# manual_master.net
KiCad netlist of a schematic drawn in EAGLE
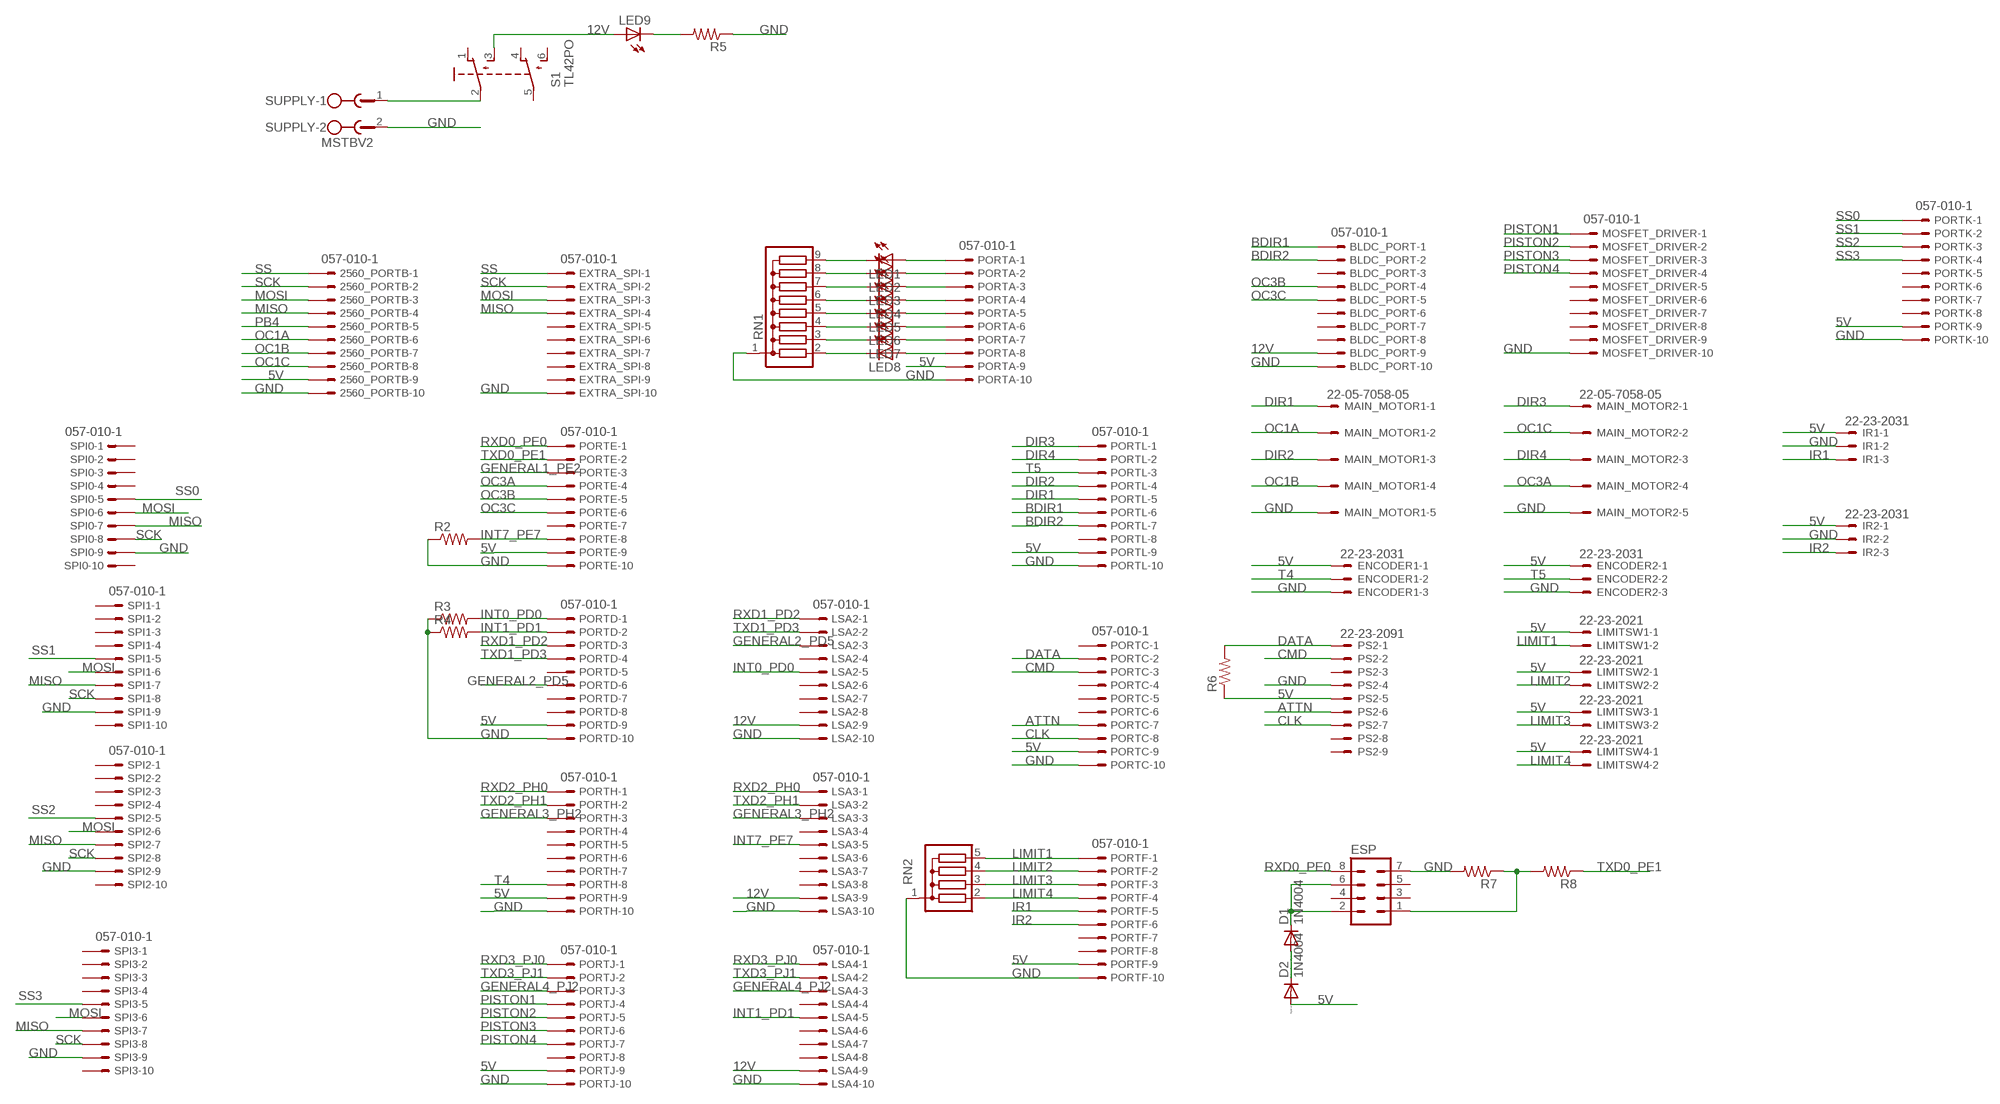
[diagram p0: schematic, sheet 1]

(export (version "E")
  (design (tool "Eeschema 10.0.6"))
  (components
    (comp (ref "2560_PORTB")
      (value "057-010-1")
      (footprint "eagle-import:057-010-1")
      (libsource (lib "eagle-import") (part "057-010-1"))
    )
    (comp (ref "BLDC_PORT")
      (value "057-010-1")
      (footprint "eagle-import:057-010-1")
      (libsource (lib "eagle-import") (part "057-010-1"))
    )
    (comp (ref "D1")
      (value "1N4004")
      (footprint "eagle-import:DO41-10")
      (libsource (lib "eagle-import") (part "1N4004"))
    )
    (comp (ref "D2")
      (value "1N4004")
      (footprint "eagle-import:DO41-10")
      (libsource (lib "eagle-import") (part "1N4004"))
    )
    (comp (ref "ENCODER1")
      (value "22-23-2031")
      (footprint "eagle-import:22-23-2031")
      (fields (field (name "MF") "MOLEX"))
      (libsource (lib "eagle-import") (part "22-23-2031"))
    )
    (comp (ref "ENCODER2")
      (value "22-23-2031")
      (footprint "eagle-import:22-23-2031")
      (fields (field (name "MF") "MOLEX"))
      (libsource (lib "eagle-import") (part "22-23-2031"))
    )
    (comp (ref "ESP")
      (value "MA04-2")
      (footprint "eagle-import:MA04-2")
      (libsource (lib "eagle-import") (part "MA04-2"))
    )
    (comp (ref "EXTRA_SPI")
      (value "057-010-1")
      (footprint "eagle-import:057-010-1")
      (libsource (lib "eagle-import") (part "057-010-1"))
    )
    (comp (ref "IR1")
      (value "22-23-2031")
      (footprint "eagle-import:22-23-2031")
      (fields (field (name "MF") "MOLEX"))
      (libsource (lib "eagle-import") (part "22-23-2031"))
    )
    (comp (ref "IR2")
      (value "22-23-2031")
      (footprint "eagle-import:22-23-2031")
      (fields (field (name "MF") "MOLEX"))
      (libsource (lib "eagle-import") (part "22-23-2031"))
    )
    (comp (ref "LED1")
      (value "LED3MM")
      (footprint "eagle-import:LED3MM")
      (libsource (lib "eagle-import") (part "LED3MM"))
    )
    (comp (ref "LED2")
      (value "LED3MM")
      (footprint "eagle-import:LED3MM")
      (libsource (lib "eagle-import") (part "LED3MM"))
    )
    (comp (ref "LED3")
      (value "LED3MM")
      (footprint "eagle-import:LED3MM")
      (libsource (lib "eagle-import") (part "LED3MM"))
    )
    (comp (ref "LED4")
      (value "LED3MM")
      (footprint "eagle-import:LED3MM")
      (libsource (lib "eagle-import") (part "LED3MM"))
    )
    (comp (ref "LED5")
      (value "LED3MM")
      (footprint "eagle-import:LED3MM")
      (libsource (lib "eagle-import") (part "LED3MM"))
    )
    (comp (ref "LED6")
      (value "LED3MM")
      (footprint "eagle-import:LED3MM")
      (libsource (lib "eagle-import") (part "LED3MM"))
    )
    (comp (ref "LED7")
      (value "LED3MM")
      (footprint "eagle-import:LED3MM")
      (libsource (lib "eagle-import") (part "LED3MM"))
    )
    (comp (ref "LED8")
      (value "LED3MM")
      (footprint "eagle-import:LED3MM")
      (libsource (lib "eagle-import") (part "LED3MM"))
    )
    (comp (ref "LED9")
      (value "LED5MM")
      (footprint "eagle-import:LED5MM")
      (libsource (lib "eagle-import") (part "LED5MM"))
    )
    (comp (ref "LIMITSW1")
      (value "22-23-2021")
      (footprint "eagle-import:22-23-2021")
      (fields (field (name "MF") "MOLEX"))
      (libsource (lib "eagle-import") (part "22-23-2021"))
    )
    (comp (ref "LIMITSW2")
      (value "22-23-2021")
      (footprint "eagle-import:22-23-2021")
      (fields (field (name "MF") "MOLEX"))
      (libsource (lib "eagle-import") (part "22-23-2021"))
    )
    (comp (ref "LIMITSW3")
      (value "22-23-2021")
      (footprint "eagle-import:22-23-2021")
      (fields (field (name "MF") "MOLEX"))
      (libsource (lib "eagle-import") (part "22-23-2021"))
    )
    (comp (ref "LIMITSW4")
      (value "22-23-2021")
      (footprint "eagle-import:22-23-2021")
      (fields (field (name "MF") "MOLEX"))
      (libsource (lib "eagle-import") (part "22-23-2021"))
    )
    (comp (ref "LSA2")
      (value "057-010-1")
      (footprint "eagle-import:057-010-1")
      (libsource (lib "eagle-import") (part "057-010-1"))
    )
    (comp (ref "LSA3")
      (value "057-010-1")
      (footprint "eagle-import:057-010-1")
      (libsource (lib "eagle-import") (part "057-010-1"))
    )
    (comp (ref "LSA4")
      (value "057-010-1")
      (footprint "eagle-import:057-010-1")
      (libsource (lib "eagle-import") (part "057-010-1"))
    )
    (comp (ref "MAIN_MOTOR1")
      (value "22-05-7058-05")
      (footprint "eagle-import:7395-05")
      (libsource (lib "eagle-import") (part "22-?-0505-7058"))
    )
    (comp (ref "MAIN_MOTOR2")
      (value "22-05-7058-05")
      (footprint "eagle-import:7395-05")
      (libsource (lib "eagle-import") (part "22-?-0505-7058"))
    )
    (comp (ref "MOSFET_DRIVER")
      (value "057-010-1")
      (footprint "eagle-import:057-010-1")
      (libsource (lib "eagle-import") (part "057-010-1"))
    )
    (comp (ref "PORTA")
      (value "057-010-1")
      (footprint "eagle-import:057-010-1")
      (libsource (lib "eagle-import") (part "057-010-1"))
    )
    (comp (ref "PORTC")
      (value "057-010-1")
      (footprint "eagle-import:057-010-1")
      (libsource (lib "eagle-import") (part "057-010-1"))
    )
    (comp (ref "PORTD")
      (value "057-010-1")
      (footprint "eagle-import:057-010-1")
      (libsource (lib "eagle-import") (part "057-010-1"))
    )
    (comp (ref "PORTE")
      (value "057-010-1")
      (footprint "eagle-import:057-010-1")
      (libsource (lib "eagle-import") (part "057-010-1"))
    )
    (comp (ref "PORTF")
      (value "057-010-1")
      (footprint "eagle-import:057-010-1")
      (libsource (lib "eagle-import") (part "057-010-1"))
    )
    (comp (ref "PORTH")
      (value "057-010-1")
      (footprint "eagle-import:057-010-1")
      (libsource (lib "eagle-import") (part "057-010-1"))
    )
    (comp (ref "PORTJ")
      (value "057-010-1")
      (footprint "eagle-import:057-010-1")
      (libsource (lib "eagle-import") (part "057-010-1"))
    )
    (comp (ref "PORTK")
      (value "057-010-1")
      (footprint "eagle-import:057-010-1")
      (libsource (lib "eagle-import") (part "057-010-1"))
    )
    (comp (ref "PORTL")
      (value "057-010-1")
      (footprint "eagle-import:057-010-1")
      (libsource (lib "eagle-import") (part "057-010-1"))
    )
    (comp (ref "PS2")
      (value "22-23-2091")
      (footprint "eagle-import:22-23-2091")
      (fields (field (name "MF") "MOLEX"))
      (libsource (lib "eagle-import") (part "22-23-2091"))
    )
    (comp (ref "R2")
      (value "R-US_0207/10")
      (footprint "eagle-import:0207_10")
      (libsource (lib "eagle-import") (part "R-US_0207/10"))
    )
    (comp (ref "R3")
      (value "R-US_0207/10")
      (footprint "eagle-import:0207_10")
      (libsource (lib "eagle-import") (part "R-US_0207/10"))
    )
    (comp (ref "R4")
      (value "R-US_0207/10")
      (footprint "eagle-import:0207_10")
      (libsource (lib "eagle-import") (part "R-US_0207/10"))
    )
    (comp (ref "R5")
      (value "R-US_0207/10")
      (footprint "eagle-import:0207_10")
      (libsource (lib "eagle-import") (part "R-US_0207/10"))
    )
    (comp (ref "R6")
      (value "R-US_0207/10")
      (footprint "eagle-import:0207_10")
      (libsource (lib "eagle-import") (part "R-US_0207/10"))
    )
    (comp (ref "R7")
      (value "R-US_0207/10")
      (footprint "eagle-import:0207_10")
      (libsource (lib "eagle-import") (part "R-US_0207/10"))
    )
    (comp (ref "R8")
      (value "R-US_0207/10")
      (footprint "eagle-import:0207_10")
      (libsource (lib "eagle-import") (part "R-US_0207/10"))
    )
    (comp (ref "RN1")
      (value "G08R")
      (footprint "eagle-import:SIL9")
      (libsource (lib "eagle-import") (part "G08R"))
    )
    (comp (ref "RN2")
      (value "G04R")
      (footprint "eagle-import:SIL5")
      (libsource (lib "eagle-import") (part "G04R"))
    )
    (comp (ref "S1")
      (value "TL42PO")
      (footprint "eagle-import:TL4XPO")
      (libsource (lib "eagle-import") (part "TL42PO"))
    )
    (comp (ref "SPI0")
      (value "057-010-1")
      (footprint "eagle-import:057-010-1")
      (libsource (lib "eagle-import") (part "057-010-1"))
    )
    (comp (ref "SPI1")
      (value "057-010-1")
      (footprint "eagle-import:057-010-1")
      (libsource (lib "eagle-import") (part "057-010-1"))
    )
    (comp (ref "SPI2")
      (value "057-010-1")
      (footprint "eagle-import:057-010-1")
      (libsource (lib "eagle-import") (part "057-010-1"))
    )
    (comp (ref "SPI3")
      (value "057-010-1")
      (footprint "eagle-import:057-010-1")
      (libsource (lib "eagle-import") (part "057-010-1"))
    )
    (comp (ref "SUPPLY")
      (value "MSTBV2")
      (footprint "eagle-import:MSTBV2")
      (fields (field (name "MPN") "MSTBV 2,5/2-GF-5.08"))
      (libsource (lib "eagle-import") (part "MSTBV2"))
    )
  )
  (nets
    (net (code "1") (name "/5V") (class "Default")
      (node (ref "2560_PORTB") (pin "9") (pinfunction "S_9") (pintype "passive"))
      (node (ref "D2") (pin "A") (pinfunction "A_A") (pintype "passive"))
      (node (ref "ENCODER1") (pin "1") (pinfunction "S_1") (pintype "passive"))
      (node (ref "ENCODER2") (pin "1") (pinfunction "S_1") (pintype "passive"))
      (node (ref "IR1") (pin "1") (pinfunction "S_1") (pintype "passive"))
      (node (ref "IR2") (pin "1") (pinfunction "S_1") (pintype "passive"))
      (node (ref "LIMITSW1") (pin "1") (pinfunction "S_1") (pintype "passive"))
      (node (ref "LIMITSW2") (pin "1") (pinfunction "S_1") (pintype "passive"))
      (node (ref "LIMITSW3") (pin "1") (pinfunction "S_1") (pintype "passive"))
      (node (ref "LIMITSW4") (pin "1") (pinfunction "S_1") (pintype "passive"))
      (node (ref "PORTA") (pin "9") (pinfunction "S_9") (pintype "passive"))
      (node (ref "PORTC") (pin "9") (pinfunction "S_9") (pintype "passive"))
      (node (ref "PORTD") (pin "9") (pinfunction "S_9") (pintype "passive"))
      (node (ref "PORTE") (pin "9") (pinfunction "S_9") (pintype "passive"))
      (node (ref "PORTF") (pin "9") (pinfunction "S_9") (pintype "passive"))
      (node (ref "PORTH") (pin "9") (pinfunction "S_9") (pintype "passive"))
      (node (ref "PORTJ") (pin "9") (pinfunction "S_9") (pintype "passive"))
      (node (ref "PORTK") (pin "9") (pinfunction "S_9") (pintype "passive"))
      (node (ref "PORTL") (pin "9") (pinfunction "S_9") (pintype "passive"))
      (node (ref "PS2") (pin "5") (pinfunction "S_5") (pintype "passive"))
      (node (ref "R6") (pin "1") (pinfunction "1_1") (pintype "passive"))
    )
    (net (code "2") (name "/12V") (class "Default")
      (node (ref "BLDC_PORT") (pin "9") (pinfunction "S_9") (pintype "passive"))
      (node (ref "LED9") (pin "A") (pinfunction "A_A") (pintype "passive"))
      (node (ref "LSA2") (pin "9") (pinfunction "S_9") (pintype "passive"))
      (node (ref "LSA3") (pin "9") (pinfunction "S_9") (pintype "passive"))
      (node (ref "LSA4") (pin "9") (pinfunction "S_9") (pintype "passive"))
      (node (ref "S1") (pin "3") (pinfunction "S_3") (pintype "passive"))
    )
    (net (code "3") (name "/ATTN") (class "Default")
      (node (ref "PORTC") (pin "7") (pinfunction "S_7") (pintype "passive"))
      (node (ref "PS2") (pin "6") (pinfunction "S_6") (pintype "passive"))
    )
    (net (code "4") (name "/BDIR1") (class "Default")
      (node (ref "BLDC_PORT") (pin "1") (pinfunction "S_1") (pintype "passive"))
      (node (ref "PORTL") (pin "6") (pinfunction "S_6") (pintype "passive"))
    )
    (net (code "5") (name "/BDIR2") (class "Default")
      (node (ref "BLDC_PORT") (pin "2") (pinfunction "S_2") (pintype "passive"))
      (node (ref "PORTL") (pin "7") (pinfunction "S_7") (pintype "passive"))
    )
    (net (code "6") (name "/CLK") (class "Default")
      (node (ref "PORTC") (pin "8") (pinfunction "S_8") (pintype "passive"))
      (node (ref "PS2") (pin "7") (pinfunction "S_7") (pintype "passive"))
    )
    (net (code "7") (name "/CMD") (class "Default")
      (node (ref "PORTC") (pin "3") (pinfunction "S_3") (pintype "passive"))
      (node (ref "PS2") (pin "2") (pinfunction "S_2") (pintype "passive"))
    )
    (net (code "8") (name "/DATA") (class "Default")
      (node (ref "PORTC") (pin "2") (pinfunction "S_2") (pintype "passive"))
      (node (ref "PS2") (pin "1") (pinfunction "S_1") (pintype "passive"))
      (node (ref "R6") (pin "2") (pinfunction "2_2") (pintype "passive"))
    )
    (net (code "9") (name "/DIR1") (class "Default")
      (node (ref "MAIN_MOTOR1") (pin "1") (pinfunction "S_1") (pintype "passive"))
      (node (ref "PORTL") (pin "5") (pinfunction "S_5") (pintype "passive"))
    )
    (net (code "10") (name "/DIR2") (class "Default")
      (node (ref "MAIN_MOTOR1") (pin "3") (pinfunction "S_3") (pintype "passive"))
      (node (ref "PORTL") (pin "4") (pinfunction "S_4") (pintype "passive"))
    )
    (net (code "11") (name "/DIR3") (class "Default")
      (node (ref "MAIN_MOTOR2") (pin "1") (pinfunction "S_1") (pintype "passive"))
      (node (ref "PORTL") (pin "1") (pinfunction "S_1") (pintype "passive"))
    )
    (net (code "12") (name "/DIR4") (class "Default")
      (node (ref "MAIN_MOTOR2") (pin "3") (pinfunction "S_3") (pintype "passive"))
      (node (ref "PORTL") (pin "2") (pinfunction "S_2") (pintype "passive"))
    )
    (net (code "13") (name "/GENERAL1_PE2") (class "Default")
      (node (ref "PORTE") (pin "3") (pinfunction "S_3") (pintype "passive"))
    )
    (net (code "14") (name "/GENERAL2_PD5") (class "Default")
      (node (ref "LSA2") (pin "3") (pinfunction "S_3") (pintype "passive"))
      (node (ref "PORTD") (pin "6") (pinfunction "S_6") (pintype "passive"))
    )
    (net (code "15") (name "/GENERAL3_PH2") (class "Default")
      (node (ref "LSA3") (pin "3") (pinfunction "S_3") (pintype "passive"))
      (node (ref "PORTH") (pin "3") (pinfunction "S_3") (pintype "passive"))
    )
    (net (code "16") (name "/GENERAL4_PJ2") (class "Default")
      (node (ref "LSA4") (pin "3") (pinfunction "S_3") (pintype "passive"))
      (node (ref "PORTJ") (pin "3") (pinfunction "S_3") (pintype "passive"))
    )
    (net (code "17") (name "/GND") (class "Default")
      (node (ref "2560_PORTB") (pin "10") (pinfunction "S_10") (pintype "passive"))
      (node (ref "BLDC_PORT") (pin "10") (pinfunction "S_10") (pintype "passive"))
      (node (ref "ENCODER1") (pin "3") (pinfunction "S_3") (pintype "passive"))
      (node (ref "ENCODER2") (pin "3") (pinfunction "S_3") (pintype "passive"))
      (node (ref "ESP") (pin "7") (pinfunction "7_7") (pintype "passive"))
      (node (ref "EXTRA_SPI") (pin "10") (pinfunction "S_10") (pintype "passive"))
      (node (ref "IR1") (pin "2") (pinfunction "S_2") (pintype "passive"))
      (node (ref "IR2") (pin "2") (pinfunction "S_2") (pintype "passive"))
      (node (ref "LSA2") (pin "10") (pinfunction "S_10") (pintype "passive"))
      (node (ref "LSA3") (pin "10") (pinfunction "S_10") (pintype "passive"))
      (node (ref "LSA4") (pin "10") (pinfunction "S_10") (pintype "passive"))
      (node (ref "MAIN_MOTOR1") (pin "5") (pinfunction "S_5") (pintype "passive"))
      (node (ref "MAIN_MOTOR2") (pin "5") (pinfunction "S_5") (pintype "passive"))
      (node (ref "MOSFET_DRIVER") (pin "10") (pinfunction "S_10") (pintype "passive"))
      (node (ref "PORTA") (pin "10") (pinfunction "S_10") (pintype "passive"))
      (node (ref "PORTC") (pin "10") (pinfunction "S_10") (pintype "passive"))
      (node (ref "PORTD") (pin "10") (pinfunction "S_10") (pintype "passive"))
      (node (ref "PORTE") (pin "10") (pinfunction "S_10") (pintype "passive"))
      (node (ref "PORTF") (pin "10") (pinfunction "S_10") (pintype "passive"))
      (node (ref "PORTH") (pin "10") (pinfunction "S_10") (pintype "passive"))
      (node (ref "PORTJ") (pin "10") (pinfunction "S_10") (pintype "passive"))
      (node (ref "PORTK") (pin "10") (pinfunction "S_10") (pintype "passive"))
      (node (ref "PORTL") (pin "10") (pinfunction "S_10") (pintype "passive"))
      (node (ref "PS2") (pin "4") (pinfunction "S_4") (pintype "passive"))
      (node (ref "R2") (pin "1") (pinfunction "1_1") (pintype "passive"))
      (node (ref "R3") (pin "1") (pinfunction "1_1") (pintype "passive"))
      (node (ref "R4") (pin "1") (pinfunction "1_1") (pintype "passive"))
      (node (ref "R5") (pin "1") (pinfunction "1_1") (pintype "passive"))
      (node (ref "R7") (pin "2") (pinfunction "2_2") (pintype "passive"))
      (node (ref "RN1") (pin "1") (pinfunction "1_1") (pintype "passive"))
      (node (ref "RN2") (pin "1") (pinfunction "1_1") (pintype "passive"))
      (node (ref "SPI0") (pin "9") (pinfunction "S_9") (pintype "passive"))
      (node (ref "SPI1") (pin "9") (pinfunction "S_9") (pintype "passive"))
      (node (ref "SPI2") (pin "9") (pinfunction "S_9") (pintype "passive"))
      (node (ref "SPI3") (pin "9") (pinfunction "S_9") (pintype "passive"))
      (node (ref "SUPPLY") (pin "2") (pinfunction "1_2") (pintype "passive"))
    )
    (net (code "18") (name "/INT0_PD0") (class "Default")
      (node (ref "LSA2") (pin "5") (pinfunction "S_5") (pintype "passive"))
      (node (ref "PORTD") (pin "1") (pinfunction "S_1") (pintype "passive"))
      (node (ref "R3") (pin "2") (pinfunction "2_2") (pintype "passive"))
    )
    (net (code "19") (name "/INT1_PD1") (class "Default")
      (node (ref "LSA4") (pin "5") (pinfunction "S_5") (pintype "passive"))
      (node (ref "PORTD") (pin "2") (pinfunction "S_2") (pintype "passive"))
      (node (ref "R4") (pin "2") (pinfunction "2_2") (pintype "passive"))
    )
    (net (code "20") (name "/INT7_PE7") (class "Default")
      (node (ref "LSA3") (pin "5") (pinfunction "S_5") (pintype "passive"))
      (node (ref "PORTE") (pin "8") (pinfunction "S_8") (pintype "passive"))
      (node (ref "R2") (pin "2") (pinfunction "2_2") (pintype "passive"))
    )
    (net (code "21") (name "/IR1") (class "Default")
      (node (ref "IR1") (pin "3") (pinfunction "S_3") (pintype "passive"))
      (node (ref "PORTF") (pin "5") (pinfunction "S_5") (pintype "passive"))
    )
    (net (code "22") (name "/IR2") (class "Default")
      (node (ref "IR2") (pin "3") (pinfunction "S_3") (pintype "passive"))
      (node (ref "PORTF") (pin "6") (pinfunction "S_6") (pintype "passive"))
    )
    (net (code "23") (name "/LIMIT1") (class "Default")
      (node (ref "LIMITSW1") (pin "2") (pinfunction "S_2") (pintype "passive"))
      (node (ref "PORTF") (pin "1") (pinfunction "S_1") (pintype "passive"))
      (node (ref "RN2") (pin "5") (pinfunction "5_5") (pintype "passive"))
    )
    (net (code "24") (name "/LIMIT2") (class "Default")
      (node (ref "LIMITSW2") (pin "2") (pinfunction "S_2") (pintype "passive"))
      (node (ref "PORTF") (pin "2") (pinfunction "S_2") (pintype "passive"))
      (node (ref "RN2") (pin "4") (pinfunction "4_4") (pintype "passive"))
    )
    (net (code "25") (name "/LIMIT3") (class "Default")
      (node (ref "LIMITSW3") (pin "2") (pinfunction "S_2") (pintype "passive"))
      (node (ref "PORTF") (pin "3") (pinfunction "S_3") (pintype "passive"))
      (node (ref "RN2") (pin "3") (pinfunction "3_3") (pintype "passive"))
    )
    (net (code "26") (name "/LIMIT4") (class "Default")
      (node (ref "LIMITSW4") (pin "2") (pinfunction "S_2") (pintype "passive"))
      (node (ref "PORTF") (pin "4") (pinfunction "S_4") (pintype "passive"))
      (node (ref "RN2") (pin "2") (pinfunction "2_2") (pintype "passive"))
    )
    (net (code "27") (name "/MISO") (class "Default")
      (node (ref "2560_PORTB") (pin "4") (pinfunction "S_4") (pintype "passive"))
      (node (ref "EXTRA_SPI") (pin "4") (pinfunction "S_4") (pintype "passive"))
      (node (ref "SPI0") (pin "7") (pinfunction "S_7") (pintype "passive"))
      (node (ref "SPI1") (pin "7") (pinfunction "S_7") (pintype "passive"))
      (node (ref "SPI2") (pin "7") (pinfunction "S_7") (pintype "passive"))
      (node (ref "SPI3") (pin "7") (pinfunction "S_7") (pintype "passive"))
    )
    (net (code "28") (name "/MOSI") (class "Default")
      (node (ref "2560_PORTB") (pin "3") (pinfunction "S_3") (pintype "passive"))
      (node (ref "EXTRA_SPI") (pin "3") (pinfunction "S_3") (pintype "passive"))
      (node (ref "SPI0") (pin "6") (pinfunction "S_6") (pintype "passive"))
      (node (ref "SPI1") (pin "6") (pinfunction "S_6") (pintype "passive"))
      (node (ref "SPI2") (pin "6") (pinfunction "S_6") (pintype "passive"))
      (node (ref "SPI3") (pin "6") (pinfunction "S_6") (pintype "passive"))
    )
    (net (code "29") (name "/OC1A") (class "Default")
      (node (ref "2560_PORTB") (pin "6") (pinfunction "S_6") (pintype "passive"))
      (node (ref "MAIN_MOTOR1") (pin "2") (pinfunction "S_2") (pintype "passive"))
    )
    (net (code "30") (name "/OC1B") (class "Default")
      (node (ref "2560_PORTB") (pin "7") (pinfunction "S_7") (pintype "passive"))
      (node (ref "MAIN_MOTOR1") (pin "4") (pinfunction "S_4") (pintype "passive"))
    )
    (net (code "31") (name "/OC1C") (class "Default")
      (node (ref "2560_PORTB") (pin "8") (pinfunction "S_8") (pintype "passive"))
      (node (ref "MAIN_MOTOR2") (pin "2") (pinfunction "S_2") (pintype "passive"))
    )
    (net (code "32") (name "/OC3A") (class "Default")
      (node (ref "MAIN_MOTOR2") (pin "4") (pinfunction "S_4") (pintype "passive"))
      (node (ref "PORTE") (pin "4") (pinfunction "S_4") (pintype "passive"))
    )
    (net (code "33") (name "/OC3B") (class "Default")
      (node (ref "BLDC_PORT") (pin "4") (pinfunction "S_4") (pintype "passive"))
      (node (ref "PORTE") (pin "5") (pinfunction "S_5") (pintype "passive"))
    )
    (net (code "34") (name "/OC3C") (class "Default")
      (node (ref "BLDC_PORT") (pin "5") (pinfunction "S_5") (pintype "passive"))
      (node (ref "PORTE") (pin "6") (pinfunction "S_6") (pintype "passive"))
    )
    (net (code "35") (name "/PB4") (class "Default")
      (node (ref "2560_PORTB") (pin "5") (pinfunction "S_5") (pintype "passive"))
    )
    (net (code "36") (name "/PISTON1") (class "Default")
      (node (ref "MOSFET_DRIVER") (pin "1") (pinfunction "S_1") (pintype "passive"))
      (node (ref "PORTJ") (pin "4") (pinfunction "S_4") (pintype "passive"))
    )
    (net (code "37") (name "/PISTON2") (class "Default")
      (node (ref "MOSFET_DRIVER") (pin "2") (pinfunction "S_2") (pintype "passive"))
      (node (ref "PORTJ") (pin "5") (pinfunction "S_5") (pintype "passive"))
    )
    (net (code "38") (name "/PISTON3") (class "Default")
      (node (ref "MOSFET_DRIVER") (pin "3") (pinfunction "S_3") (pintype "passive"))
      (node (ref "PORTJ") (pin "6") (pinfunction "S_6") (pintype "passive"))
    )
    (net (code "39") (name "/PISTON4") (class "Default")
      (node (ref "MOSFET_DRIVER") (pin "4") (pinfunction "S_4") (pintype "passive"))
      (node (ref "PORTJ") (pin "7") (pinfunction "S_7") (pintype "passive"))
    )
    (net (code "40") (name "/RXD0_PE0") (class "Default")
      (node (ref "ESP") (pin "8") (pinfunction "8_8") (pintype "passive"))
      (node (ref "PORTE") (pin "1") (pinfunction "S_1") (pintype "passive"))
    )
    (net (code "41") (name "/RXD1_PD2") (class "Default")
      (node (ref "LSA2") (pin "1") (pinfunction "S_1") (pintype "passive"))
      (node (ref "PORTD") (pin "3") (pinfunction "S_3") (pintype "passive"))
    )
    (net (code "42") (name "/RXD2_PH0") (class "Default")
      (node (ref "LSA3") (pin "1") (pinfunction "S_1") (pintype "passive"))
      (node (ref "PORTH") (pin "1") (pinfunction "S_1") (pintype "passive"))
    )
    (net (code "43") (name "/RXD3_PJ0") (class "Default")
      (node (ref "LSA4") (pin "1") (pinfunction "S_1") (pintype "passive"))
      (node (ref "PORTJ") (pin "1") (pinfunction "S_1") (pintype "passive"))
    )
    (net (code "44") (name "/SCK") (class "Default")
      (node (ref "2560_PORTB") (pin "2") (pinfunction "S_2") (pintype "passive"))
      (node (ref "EXTRA_SPI") (pin "2") (pinfunction "S_2") (pintype "passive"))
      (node (ref "SPI0") (pin "8") (pinfunction "S_8") (pintype "passive"))
      (node (ref "SPI1") (pin "8") (pinfunction "S_8") (pintype "passive"))
      (node (ref "SPI2") (pin "8") (pinfunction "S_8") (pintype "passive"))
      (node (ref "SPI3") (pin "8") (pinfunction "S_8") (pintype "passive"))
    )
    (net (code "45") (name "/SS") (class "Default")
      (node (ref "2560_PORTB") (pin "1") (pinfunction "S_1") (pintype "passive"))
      (node (ref "EXTRA_SPI") (pin "1") (pinfunction "S_1") (pintype "passive"))
    )
    (net (code "46") (name "/SS0") (class "Default")
      (node (ref "PORTK") (pin "1") (pinfunction "S_1") (pintype "passive"))
      (node (ref "SPI0") (pin "5") (pinfunction "S_5") (pintype "passive"))
    )
    (net (code "47") (name "/SS1") (class "Default")
      (node (ref "PORTK") (pin "2") (pinfunction "S_2") (pintype "passive"))
      (node (ref "SPI1") (pin "5") (pinfunction "S_5") (pintype "passive"))
    )
    (net (code "48") (name "/SS2") (class "Default")
      (node (ref "PORTK") (pin "3") (pinfunction "S_3") (pintype "passive"))
      (node (ref "SPI2") (pin "5") (pinfunction "S_5") (pintype "passive"))
    )
    (net (code "49") (name "/SS3") (class "Default")
      (node (ref "PORTK") (pin "4") (pinfunction "S_4") (pintype "passive"))
      (node (ref "SPI3") (pin "5") (pinfunction "S_5") (pintype "passive"))
    )
    (net (code "50") (name "/T4") (class "Default")
      (node (ref "ENCODER1") (pin "2") (pinfunction "S_2") (pintype "passive"))
      (node (ref "PORTH") (pin "8") (pinfunction "S_8") (pintype "passive"))
    )
    (net (code "51") (name "/T5") (class "Default")
      (node (ref "ENCODER2") (pin "2") (pinfunction "S_2") (pintype "passive"))
      (node (ref "PORTL") (pin "3") (pinfunction "S_3") (pintype "passive"))
    )
    (net (code "52") (name "/TXD0_PE1") (class "Default")
      (node (ref "PORTE") (pin "2") (pinfunction "S_2") (pintype "passive"))
      (node (ref "R8") (pin "1") (pinfunction "1_1") (pintype "passive"))
    )
    (net (code "53") (name "/TXD1_PD3") (class "Default")
      (node (ref "LSA2") (pin "2") (pinfunction "S_2") (pintype "passive"))
      (node (ref "PORTD") (pin "4") (pinfunction "S_4") (pintype "passive"))
    )
    (net (code "54") (name "/TXD2_PH1") (class "Default")
      (node (ref "LSA3") (pin "2") (pinfunction "S_2") (pintype "passive"))
      (node (ref "PORTH") (pin "2") (pinfunction "S_2") (pintype "passive"))
    )
    (net (code "55") (name "/TXD3_PJ1") (class "Default")
      (node (ref "LSA4") (pin "2") (pinfunction "S_2") (pintype "passive"))
      (node (ref "PORTJ") (pin "2") (pinfunction "S_2") (pintype "passive"))
    )
    (net (code "56") (name "Net-(D1-PadA)") (class "Default")
      (node (ref "D1") (pin "A") (pinfunction "A_A") (pintype "passive"))
      (node (ref "D2") (pin "C") (pinfunction "C_C") (pintype "passive"))
    )
    (net (code "57") (name "Net-(D1-PadC)") (class "Default")
      (node (ref "D1") (pin "C") (pinfunction "C_C") (pintype "passive"))
      (node (ref "ESP") (pin "2") (pinfunction "2_2") (pintype "passive"))
      (node (ref "ESP") (pin "6") (pinfunction "6_6") (pintype "passive"))
    )
    (net (code "58") (name "Net-(ESP-Pad1)") (class "Default")
      (node (ref "ESP") (pin "1") (pinfunction "1_1") (pintype "passive"))
      (node (ref "R7") (pin "1") (pinfunction "1_1") (pintype "passive"))
      (node (ref "R8") (pin "2") (pinfunction "2_2") (pintype "passive"))
    )
    (net (code "59") (name "Net-(LED1-C)") (class "Default")
      (node (ref "LED1") (pin "K") (pinfunction "C_K") (pintype "passive"))
      (node (ref "RN1") (pin "9") (pinfunction "9_9") (pintype "passive"))
    )
    (net (code "60") (name "Net-(LED2-C)") (class "Default")
      (node (ref "LED2") (pin "K") (pinfunction "C_K") (pintype "passive"))
      (node (ref "RN1") (pin "8") (pinfunction "8_8") (pintype "passive"))
    )
    (net (code "61") (name "Net-(LED3-C)") (class "Default")
      (node (ref "LED3") (pin "K") (pinfunction "C_K") (pintype "passive"))
      (node (ref "RN1") (pin "7") (pinfunction "7_7") (pintype "passive"))
    )
    (net (code "62") (name "Net-(LED4-C)") (class "Default")
      (node (ref "LED4") (pin "K") (pinfunction "C_K") (pintype "passive"))
      (node (ref "RN1") (pin "6") (pinfunction "6_6") (pintype "passive"))
    )
    (net (code "63") (name "Net-(LED5-C)") (class "Default")
      (node (ref "LED5") (pin "K") (pinfunction "C_K") (pintype "passive"))
      (node (ref "RN1") (pin "5") (pinfunction "5_5") (pintype "passive"))
    )
    (net (code "64") (name "Net-(LED6-C)") (class "Default")
      (node (ref "LED6") (pin "K") (pinfunction "C_K") (pintype "passive"))
      (node (ref "RN1") (pin "4") (pinfunction "4_4") (pintype "passive"))
    )
    (net (code "65") (name "Net-(LED7-C)") (class "Default")
      (node (ref "LED7") (pin "K") (pinfunction "C_K") (pintype "passive"))
      (node (ref "RN1") (pin "3") (pinfunction "3_3") (pintype "passive"))
    )
    (net (code "66") (name "Net-(LED8-C)") (class "Default")
      (node (ref "LED8") (pin "K") (pinfunction "C_K") (pintype "passive"))
      (node (ref "RN1") (pin "2") (pinfunction "2_2") (pintype "passive"))
    )
    (net (code "67") (name "Net-(LED9-C)") (class "Default")
      (node (ref "LED9") (pin "K") (pinfunction "C_K") (pintype "passive"))
      (node (ref "R5") (pin "2") (pinfunction "2_2") (pintype "passive"))
    )
    (net (code "68") (name "Net-(PORTAA-S)") (class "Default")
      (node (ref "LED1") (pin "A") (pinfunction "A_A") (pintype "passive"))
      (node (ref "PORTA") (pin "1") (pinfunction "S_1") (pintype "passive"))
    )
    (net (code "69") (name "Net-(PORTAC-S)") (class "Default")
      (node (ref "LED2") (pin "A") (pinfunction "A_A") (pintype "passive"))
      (node (ref "PORTA") (pin "2") (pinfunction "S_2") (pintype "passive"))
    )
    (net (code "70") (name "Net-(PORTAD-S)") (class "Default")
      (node (ref "LED3") (pin "A") (pinfunction "A_A") (pintype "passive"))
      (node (ref "PORTA") (pin "3") (pinfunction "S_3") (pintype "passive"))
    )
    (net (code "71") (name "Net-(PORTAE-S)") (class "Default")
      (node (ref "LED4") (pin "A") (pinfunction "A_A") (pintype "passive"))
      (node (ref "PORTA") (pin "4") (pinfunction "S_4") (pintype "passive"))
    )
    (net (code "72") (name "Net-(PORTAF-S)") (class "Default")
      (node (ref "LED5") (pin "A") (pinfunction "A_A") (pintype "passive"))
      (node (ref "PORTA") (pin "5") (pinfunction "S_5") (pintype "passive"))
    )
    (net (code "73") (name "Net-(PORTAG-S)") (class "Default")
      (node (ref "LED6") (pin "A") (pinfunction "A_A") (pintype "passive"))
      (node (ref "PORTA") (pin "6") (pinfunction "S_6") (pintype "passive"))
    )
    (net (code "74") (name "Net-(PORTAH-S)") (class "Default")
      (node (ref "LED7") (pin "A") (pinfunction "A_A") (pintype "passive"))
      (node (ref "PORTA") (pin "7") (pinfunction "S_7") (pintype "passive"))
    )
    (net (code "75") (name "Net-(PORTAI-S)") (class "Default")
      (node (ref "LED8") (pin "A") (pinfunction "A_A") (pintype "passive"))
      (node (ref "PORTA") (pin "8") (pinfunction "S_8") (pintype "passive"))
    )
    (net (code "76") (name "Net-(S1-P)") (class "Default")
      (node (ref "S1") (pin "2") (pinfunction "P_2") (pintype "passive"))
      (node (ref "SUPPLY") (pin "1") (pinfunction "1_1") (pintype "passive"))
    )
    (net (code "77") (name "unconnected-(BLDC_PORTD-S-Pad3)") (class "Default")
      (node (ref "BLDC_PORT") (pin "3") (pinfunction "S_3") (pintype "passive"))
    )
    (net (code "78") (name "unconnected-(BLDC_PORTG-S-Pad6)") (class "Default")
      (node (ref "BLDC_PORT") (pin "6") (pinfunction "S_6") (pintype "passive"))
    )
    (net (code "79") (name "unconnected-(BLDC_PORTH-S-Pad7)") (class "Default")
      (node (ref "BLDC_PORT") (pin "7") (pinfunction "S_7") (pintype "passive"))
    )
    (net (code "80") (name "unconnected-(BLDC_PORTI-S-Pad8)") (class "Default")
      (node (ref "BLDC_PORT") (pin "8") (pinfunction "S_8") (pintype "passive"))
    )
    (net (code "81") (name "unconnected-(ESP-Pad3)") (class "Default")
      (node (ref "ESP") (pin "3") (pinfunction "3_3") (pintype "passive"))
    )
    (net (code "82") (name "unconnected-(ESP-Pad4)") (class "Default")
      (node (ref "ESP") (pin "4") (pinfunction "4_4") (pintype "passive"))
    )
    (net (code "83") (name "unconnected-(ESP-Pad5)") (class "Default")
      (node (ref "ESP") (pin "5") (pinfunction "5_5") (pintype "passive"))
    )
    (net (code "84") (name "unconnected-(EXTRA_SPIF-S-Pad5)") (class "Default")
      (node (ref "EXTRA_SPI") (pin "5") (pinfunction "S_5") (pintype "passive"))
    )
    (net (code "85") (name "unconnected-(EXTRA_SPIG-S-Pad6)") (class "Default")
      (node (ref "EXTRA_SPI") (pin "6") (pinfunction "S_6") (pintype "passive"))
    )
    (net (code "86") (name "unconnected-(EXTRA_SPIH-S-Pad7)") (class "Default")
      (node (ref "EXTRA_SPI") (pin "7") (pinfunction "S_7") (pintype "passive"))
    )
    (net (code "87") (name "unconnected-(EXTRA_SPII-S-Pad8)") (class "Default")
      (node (ref "EXTRA_SPI") (pin "8") (pinfunction "S_8") (pintype "passive"))
    )
    (net (code "88") (name "unconnected-(EXTRA_SPIJ-S-Pad9)") (class "Default")
      (node (ref "EXTRA_SPI") (pin "9") (pinfunction "S_9") (pintype "passive"))
    )
    (net (code "89") (name "unconnected-(LSA2E-S-Pad4)") (class "Default")
      (node (ref "LSA2") (pin "4") (pinfunction "S_4") (pintype "passive"))
    )
    (net (code "90") (name "unconnected-(LSA2G-S-Pad6)") (class "Default")
      (node (ref "LSA2") (pin "6") (pinfunction "S_6") (pintype "passive"))
    )
    (net (code "91") (name "unconnected-(LSA2H-S-Pad7)") (class "Default")
      (node (ref "LSA2") (pin "7") (pinfunction "S_7") (pintype "passive"))
    )
    (net (code "92") (name "unconnected-(LSA2I-S-Pad8)") (class "Default")
      (node (ref "LSA2") (pin "8") (pinfunction "S_8") (pintype "passive"))
    )
    (net (code "93") (name "unconnected-(LSA3E-S-Pad4)") (class "Default")
      (node (ref "LSA3") (pin "4") (pinfunction "S_4") (pintype "passive"))
    )
    (net (code "94") (name "unconnected-(LSA3G-S-Pad6)") (class "Default")
      (node (ref "LSA3") (pin "6") (pinfunction "S_6") (pintype "passive"))
    )
    (net (code "95") (name "unconnected-(LSA3H-S-Pad7)") (class "Default")
      (node (ref "LSA3") (pin "7") (pinfunction "S_7") (pintype "passive"))
    )
    (net (code "96") (name "unconnected-(LSA3I-S-Pad8)") (class "Default")
      (node (ref "LSA3") (pin "8") (pinfunction "S_8") (pintype "passive"))
    )
    (net (code "97") (name "unconnected-(LSA4E-S-Pad4)") (class "Default")
      (node (ref "LSA4") (pin "4") (pinfunction "S_4") (pintype "passive"))
    )
    (net (code "98") (name "unconnected-(LSA4G-S-Pad6)") (class "Default")
      (node (ref "LSA4") (pin "6") (pinfunction "S_6") (pintype "passive"))
    )
    (net (code "99") (name "unconnected-(LSA4H-S-Pad7)") (class "Default")
      (node (ref "LSA4") (pin "7") (pinfunction "S_7") (pintype "passive"))
    )
    (net (code "100") (name "unconnected-(LSA4I-S-Pad8)") (class "Default")
      (node (ref "LSA4") (pin "8") (pinfunction "S_8") (pintype "passive"))
    )
    (net (code "101") (name "unconnected-(MOSFET_DRIVERF-S-Pad5)") (class "Default")
      (node (ref "MOSFET_DRIVER") (pin "5") (pinfunction "S_5") (pintype "passive"))
    )
    (net (code "102") (name "unconnected-(MOSFET_DRIVERG-S-Pad6)") (class "Default")
      (node (ref "MOSFET_DRIVER") (pin "6") (pinfunction "S_6") (pintype "passive"))
    )
    (net (code "103") (name "unconnected-(MOSFET_DRIVERH-S-Pad7)") (class "Default")
      (node (ref "MOSFET_DRIVER") (pin "7") (pinfunction "S_7") (pintype "passive"))
    )
    (net (code "104") (name "unconnected-(MOSFET_DRIVERI-S-Pad8)") (class "Default")
      (node (ref "MOSFET_DRIVER") (pin "8") (pinfunction "S_8") (pintype "passive"))
    )
    (net (code "105") (name "unconnected-(MOSFET_DRIVERJ-S-Pad9)") (class "Default")
      (node (ref "MOSFET_DRIVER") (pin "9") (pinfunction "S_9") (pintype "passive"))
    )
    (net (code "106") (name "unconnected-(PORTCA-S-Pad1)") (class "Default")
      (node (ref "PORTC") (pin "1") (pinfunction "S_1") (pintype "passive"))
    )
    (net (code "107") (name "unconnected-(PORTCE-S-Pad4)") (class "Default")
      (node (ref "PORTC") (pin "4") (pinfunction "S_4") (pintype "passive"))
    )
    (net (code "108") (name "unconnected-(PORTCF-S-Pad5)") (class "Default")
      (node (ref "PORTC") (pin "5") (pinfunction "S_5") (pintype "passive"))
    )
    (net (code "109") (name "unconnected-(PORTCG-S-Pad6)") (class "Default")
      (node (ref "PORTC") (pin "6") (pinfunction "S_6") (pintype "passive"))
    )
    (net (code "110") (name "unconnected-(PORTDF-S-Pad5)") (class "Default")
      (node (ref "PORTD") (pin "5") (pinfunction "S_5") (pintype "passive"))
    )
    (net (code "111") (name "unconnected-(PORTDH-S-Pad7)") (class "Default")
      (node (ref "PORTD") (pin "7") (pinfunction "S_7") (pintype "passive"))
    )
    (net (code "112") (name "unconnected-(PORTDI-S-Pad8)") (class "Default")
      (node (ref "PORTD") (pin "8") (pinfunction "S_8") (pintype "passive"))
    )
    (net (code "113") (name "unconnected-(PORTEH-S-Pad7)") (class "Default")
      (node (ref "PORTE") (pin "7") (pinfunction "S_7") (pintype "passive"))
    )
    (net (code "114") (name "unconnected-(PORTFH-S-Pad7)") (class "Default")
      (node (ref "PORTF") (pin "7") (pinfunction "S_7") (pintype "passive"))
    )
    (net (code "115") (name "unconnected-(PORTFI-S-Pad8)") (class "Default")
      (node (ref "PORTF") (pin "8") (pinfunction "S_8") (pintype "passive"))
    )
    (net (code "116") (name "unconnected-(PORTHE-S-Pad4)") (class "Default")
      (node (ref "PORTH") (pin "4") (pinfunction "S_4") (pintype "passive"))
    )
    (net (code "117") (name "unconnected-(PORTHF-S-Pad5)") (class "Default")
      (node (ref "PORTH") (pin "5") (pinfunction "S_5") (pintype "passive"))
    )
    (net (code "118") (name "unconnected-(PORTHG-S-Pad6)") (class "Default")
      (node (ref "PORTH") (pin "6") (pinfunction "S_6") (pintype "passive"))
    )
    (net (code "119") (name "unconnected-(PORTHH-S-Pad7)") (class "Default")
      (node (ref "PORTH") (pin "7") (pinfunction "S_7") (pintype "passive"))
    )
    (net (code "120") (name "unconnected-(PORTJI-S-Pad8)") (class "Default")
      (node (ref "PORTJ") (pin "8") (pinfunction "S_8") (pintype "passive"))
    )
    (net (code "121") (name "unconnected-(PORTKF-S-Pad5)") (class "Default")
      (node (ref "PORTK") (pin "5") (pinfunction "S_5") (pintype "passive"))
    )
    (net (code "122") (name "unconnected-(PORTKG-S-Pad6)") (class "Default")
      (node (ref "PORTK") (pin "6") (pinfunction "S_6") (pintype "passive"))
    )
    (net (code "123") (name "unconnected-(PORTKH-S-Pad7)") (class "Default")
      (node (ref "PORTK") (pin "7") (pinfunction "S_7") (pintype "passive"))
    )
    (net (code "124") (name "unconnected-(PORTKI-S-Pad8)") (class "Default")
      (node (ref "PORTK") (pin "8") (pinfunction "S_8") (pintype "passive"))
    )
    (net (code "125") (name "unconnected-(PORTLI-S-Pad8)") (class "Default")
      (node (ref "PORTL") (pin "8") (pinfunction "S_8") (pintype "passive"))
    )
    (net (code "126") (name "unconnected-(PS2C-S-Pad3)") (class "Default")
      (node (ref "PS2") (pin "3") (pinfunction "S_3") (pintype "passive"))
    )
    (net (code "127") (name "unconnected-(PS2H-S-Pad8)") (class "Default")
      (node (ref "PS2") (pin "8") (pinfunction "S_8") (pintype "passive"))
    )
    (net (code "128") (name "unconnected-(PS2I-S-Pad9)") (class "Default")
      (node (ref "PS2") (pin "9") (pinfunction "S_9") (pintype "passive"))
    )
    (net (code "129") (name "unconnected-(S1-O-Pad1)") (class "Default")
      (node (ref "S1") (pin "1") (pinfunction "O_1") (pintype "passive"))
    )
    (net (code "130") (name "unconnected-(S1-O1-Pad4)") (class "Default")
      (node (ref "S1") (pin "4") (pinfunction "O1_4") (pintype "passive"))
    )
    (net (code "131") (name "unconnected-(S1-P1-Pad5)") (class "Default")
      (node (ref "S1") (pin "5") (pinfunction "P1_5") (pintype "passive"))
    )
    (net (code "132") (name "unconnected-(S1-S1-Pad6)") (class "Default")
      (node (ref "S1") (pin "6") (pinfunction "S1_6") (pintype "passive"))
    )
    (net (code "133") (name "unconnected-(SPI0A-S-Pad1)") (class "Default")
      (node (ref "SPI0") (pin "1") (pinfunction "S_1") (pintype "passive"))
    )
    (net (code "134") (name "unconnected-(SPI0B-S-Pad10)") (class "Default")
      (node (ref "SPI0") (pin "10") (pinfunction "S_10") (pintype "passive"))
    )
    (net (code "135") (name "unconnected-(SPI0C-S-Pad2)") (class "Default")
      (node (ref "SPI0") (pin "2") (pinfunction "S_2") (pintype "passive"))
    )
    (net (code "136") (name "unconnected-(SPI0D-S-Pad3)") (class "Default")
      (node (ref "SPI0") (pin "3") (pinfunction "S_3") (pintype "passive"))
    )
    (net (code "137") (name "unconnected-(SPI0E-S-Pad4)") (class "Default")
      (node (ref "SPI0") (pin "4") (pinfunction "S_4") (pintype "passive"))
    )
    (net (code "138") (name "unconnected-(SPI1A-S-Pad1)") (class "Default")
      (node (ref "SPI1") (pin "1") (pinfunction "S_1") (pintype "passive"))
    )
    (net (code "139") (name "unconnected-(SPI1B-S-Pad10)") (class "Default")
      (node (ref "SPI1") (pin "10") (pinfunction "S_10") (pintype "passive"))
    )
    (net (code "140") (name "unconnected-(SPI1C-S-Pad2)") (class "Default")
      (node (ref "SPI1") (pin "2") (pinfunction "S_2") (pintype "passive"))
    )
    (net (code "141") (name "unconnected-(SPI1D-S-Pad3)") (class "Default")
      (node (ref "SPI1") (pin "3") (pinfunction "S_3") (pintype "passive"))
    )
    (net (code "142") (name "unconnected-(SPI1E-S-Pad4)") (class "Default")
      (node (ref "SPI1") (pin "4") (pinfunction "S_4") (pintype "passive"))
    )
    (net (code "143") (name "unconnected-(SPI2A-S-Pad1)") (class "Default")
      (node (ref "SPI2") (pin "1") (pinfunction "S_1") (pintype "passive"))
    )
    (net (code "144") (name "unconnected-(SPI2B-S-Pad10)") (class "Default")
      (node (ref "SPI2") (pin "10") (pinfunction "S_10") (pintype "passive"))
    )
    (net (code "145") (name "unconnected-(SPI2C-S-Pad2)") (class "Default")
      (node (ref "SPI2") (pin "2") (pinfunction "S_2") (pintype "passive"))
    )
    (net (code "146") (name "unconnected-(SPI2D-S-Pad3)") (class "Default")
      (node (ref "SPI2") (pin "3") (pinfunction "S_3") (pintype "passive"))
    )
    (net (code "147") (name "unconnected-(SPI2E-S-Pad4)") (class "Default")
      (node (ref "SPI2") (pin "4") (pinfunction "S_4") (pintype "passive"))
    )
    (net (code "148") (name "unconnected-(SPI3A-S-Pad1)") (class "Default")
      (node (ref "SPI3") (pin "1") (pinfunction "S_1") (pintype "passive"))
    )
    (net (code "149") (name "unconnected-(SPI3B-S-Pad10)") (class "Default")
      (node (ref "SPI3") (pin "10") (pinfunction "S_10") (pintype "passive"))
    )
    (net (code "150") (name "unconnected-(SPI3C-S-Pad2)") (class "Default")
      (node (ref "SPI3") (pin "2") (pinfunction "S_2") (pintype "passive"))
    )
    (net (code "151") (name "unconnected-(SPI3D-S-Pad3)") (class "Default")
      (node (ref "SPI3") (pin "3") (pinfunction "S_3") (pintype "passive"))
    )
    (net (code "152") (name "unconnected-(SPI3E-S-Pad4)") (class "Default")
      (node (ref "SPI3") (pin "4") (pinfunction "S_4") (pintype "passive"))
    )
  )
)
